# SCFschem.net
KiCad netlist of a schematic drawn in EAGLE
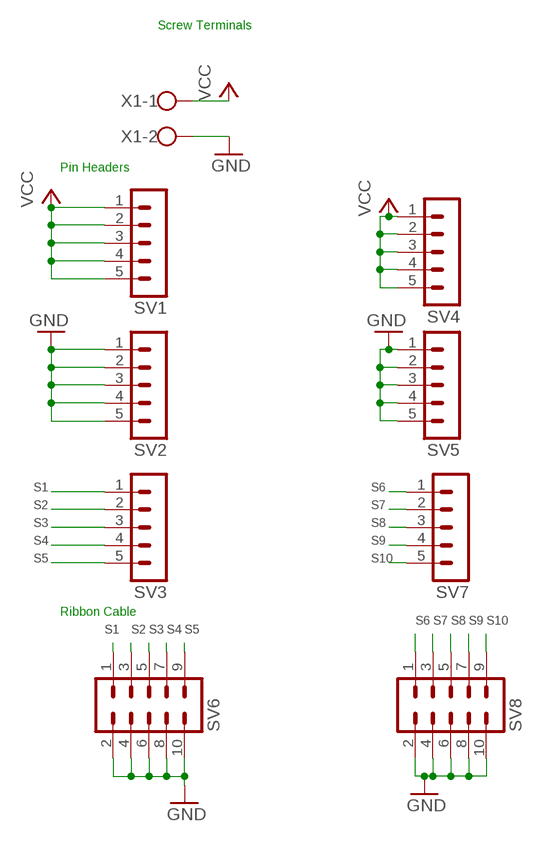
[diagram p0: schematic, sheet 1]

(export (version "E")
  (design (tool "Eeschema 10.0.6"))
  (components
    (comp (ref "SV1")
      (value "MA05-1")
      (footprint "eagle-import:MA05-1")
      (libsource (lib "eagle-import") (part "MA05-1"))
    )
    (comp (ref "SV2")
      (value "MA05-1")
      (footprint "eagle-import:MA05-1")
      (libsource (lib "eagle-import") (part "MA05-1"))
    )
    (comp (ref "SV3")
      (value "MA05-1")
      (footprint "eagle-import:MA05-1")
      (libsource (lib "eagle-import") (part "MA05-1"))
    )
    (comp (ref "SV4")
      (value "MA05-1")
      (footprint "eagle-import:MA05-1")
      (libsource (lib "eagle-import") (part "MA05-1"))
    )
    (comp (ref "SV5")
      (value "MA05-1")
      (footprint "eagle-import:MA05-1")
      (libsource (lib "eagle-import") (part "MA05-1"))
    )
    (comp (ref "SV6")
      (value "MA05-2")
      (footprint "eagle-import:MA05-2")
      (libsource (lib "eagle-import") (part "MA05-2"))
    )
    (comp (ref "SV7")
      (value "MA05-1")
      (footprint "eagle-import:MA05-1")
      (libsource (lib "eagle-import") (part "MA05-1"))
    )
    (comp (ref "SV8")
      (value "MA05-2")
      (footprint "eagle-import:MA05-2")
      (libsource (lib "eagle-import") (part "MA05-2"))
    )
    (comp (ref "X1")
      (value "1X02_5MM_SCREW")
      (footprint "eagle-import:W237-102")
      (fields (field (name "MPN") "237-102"))
      (libsource (lib "eagle-import") (part "1X02_5MM_SCREW"))
    )
  )
  (nets
    (net (code "1") (name "/S1") (class "Default")
      (node (ref "SV3") (pin "1") (pinfunction "1_1") (pintype "passive"))
      (node (ref "SV6") (pin "1") (pinfunction "1_1") (pintype "passive"))
    )
    (net (code "2") (name "/S2") (class "Default")
      (node (ref "SV3") (pin "2") (pinfunction "2_2") (pintype "passive"))
      (node (ref "SV6") (pin "3") (pinfunction "3_3") (pintype "passive"))
    )
    (net (code "3") (name "/S3") (class "Default")
      (node (ref "SV3") (pin "3") (pinfunction "3_3") (pintype "passive"))
      (node (ref "SV6") (pin "5") (pinfunction "5_5") (pintype "passive"))
    )
    (net (code "4") (name "/S4") (class "Default")
      (node (ref "SV3") (pin "4") (pinfunction "4_4") (pintype "passive"))
      (node (ref "SV6") (pin "7") (pinfunction "7_7") (pintype "passive"))
    )
    (net (code "5") (name "/S5") (class "Default")
      (node (ref "SV3") (pin "5") (pinfunction "5_5") (pintype "passive"))
      (node (ref "SV6") (pin "9") (pinfunction "9_9") (pintype "passive"))
    )
    (net (code "6") (name "/S6") (class "Default")
      (node (ref "SV7") (pin "1") (pinfunction "1_1") (pintype "passive"))
      (node (ref "SV8") (pin "1") (pinfunction "1_1") (pintype "passive"))
    )
    (net (code "7") (name "/S7") (class "Default")
      (node (ref "SV7") (pin "2") (pinfunction "2_2") (pintype "passive"))
      (node (ref "SV8") (pin "3") (pinfunction "3_3") (pintype "passive"))
    )
    (net (code "8") (name "/S8") (class "Default")
      (node (ref "SV7") (pin "3") (pinfunction "3_3") (pintype "passive"))
      (node (ref "SV8") (pin "5") (pinfunction "5_5") (pintype "passive"))
    )
    (net (code "9") (name "/S9") (class "Default")
      (node (ref "SV7") (pin "4") (pinfunction "4_4") (pintype "passive"))
      (node (ref "SV8") (pin "7") (pinfunction "7_7") (pintype "passive"))
    )
    (net (code "10") (name "/S10") (class "Default")
      (node (ref "SV7") (pin "5") (pinfunction "5_5") (pintype "passive"))
      (node (ref "SV8") (pin "9") (pinfunction "9_9") (pintype "passive"))
    )
    (net (code "11") (name "GND") (class "Default")
      (node (ref "SV2") (pin "1") (pinfunction "1_1") (pintype "passive"))
      (node (ref "SV2") (pin "2") (pinfunction "2_2") (pintype "passive"))
      (node (ref "SV2") (pin "3") (pinfunction "3_3") (pintype "passive"))
      (node (ref "SV2") (pin "4") (pinfunction "4_4") (pintype "passive"))
      (node (ref "SV2") (pin "5") (pinfunction "5_5") (pintype "passive"))
      (node (ref "SV5") (pin "1") (pinfunction "1_1") (pintype "passive"))
      (node (ref "SV5") (pin "2") (pinfunction "2_2") (pintype "passive"))
      (node (ref "SV5") (pin "3") (pinfunction "3_3") (pintype "passive"))
      (node (ref "SV5") (pin "4") (pinfunction "4_4") (pintype "passive"))
      (node (ref "SV5") (pin "5") (pinfunction "5_5") (pintype "passive"))
      (node (ref "SV6") (pin "10") (pinfunction "10_10") (pintype "passive"))
      (node (ref "SV6") (pin "2") (pinfunction "2_2") (pintype "passive"))
      (node (ref "SV6") (pin "4") (pinfunction "4_4") (pintype "passive"))
      (node (ref "SV6") (pin "6") (pinfunction "6_6") (pintype "passive"))
      (node (ref "SV6") (pin "8") (pinfunction "8_8") (pintype "passive"))
      (node (ref "SV8") (pin "10") (pinfunction "10_10") (pintype "passive"))
      (node (ref "SV8") (pin "2") (pinfunction "2_2") (pintype "passive"))
      (node (ref "SV8") (pin "4") (pinfunction "4_4") (pintype "passive"))
      (node (ref "SV8") (pin "6") (pinfunction "6_6") (pintype "passive"))
      (node (ref "SV8") (pin "8") (pinfunction "8_8") (pintype "passive"))
      (node (ref "X1") (pin "2") (pinfunction "KL_2") (pintype "passive"))
    )
    (net (code "12") (name "VCC") (class "Default")
      (node (ref "SV1") (pin "1") (pinfunction "1_1") (pintype "passive"))
      (node (ref "SV1") (pin "2") (pinfunction "2_2") (pintype "passive"))
      (node (ref "SV1") (pin "3") (pinfunction "3_3") (pintype "passive"))
      (node (ref "SV1") (pin "4") (pinfunction "4_4") (pintype "passive"))
      (node (ref "SV1") (pin "5") (pinfunction "5_5") (pintype "passive"))
      (node (ref "SV4") (pin "1") (pinfunction "1_1") (pintype "passive"))
      (node (ref "SV4") (pin "2") (pinfunction "2_2") (pintype "passive"))
      (node (ref "SV4") (pin "3") (pinfunction "3_3") (pintype "passive"))
      (node (ref "SV4") (pin "4") (pinfunction "4_4") (pintype "passive"))
      (node (ref "SV4") (pin "5") (pinfunction "5_5") (pintype "passive"))
      (node (ref "X1") (pin "1") (pinfunction "KL_1") (pintype "passive"))
    )
  )
)
